# dcdr_3_0.net
KiCad netlist of a schematic drawn in EAGLE
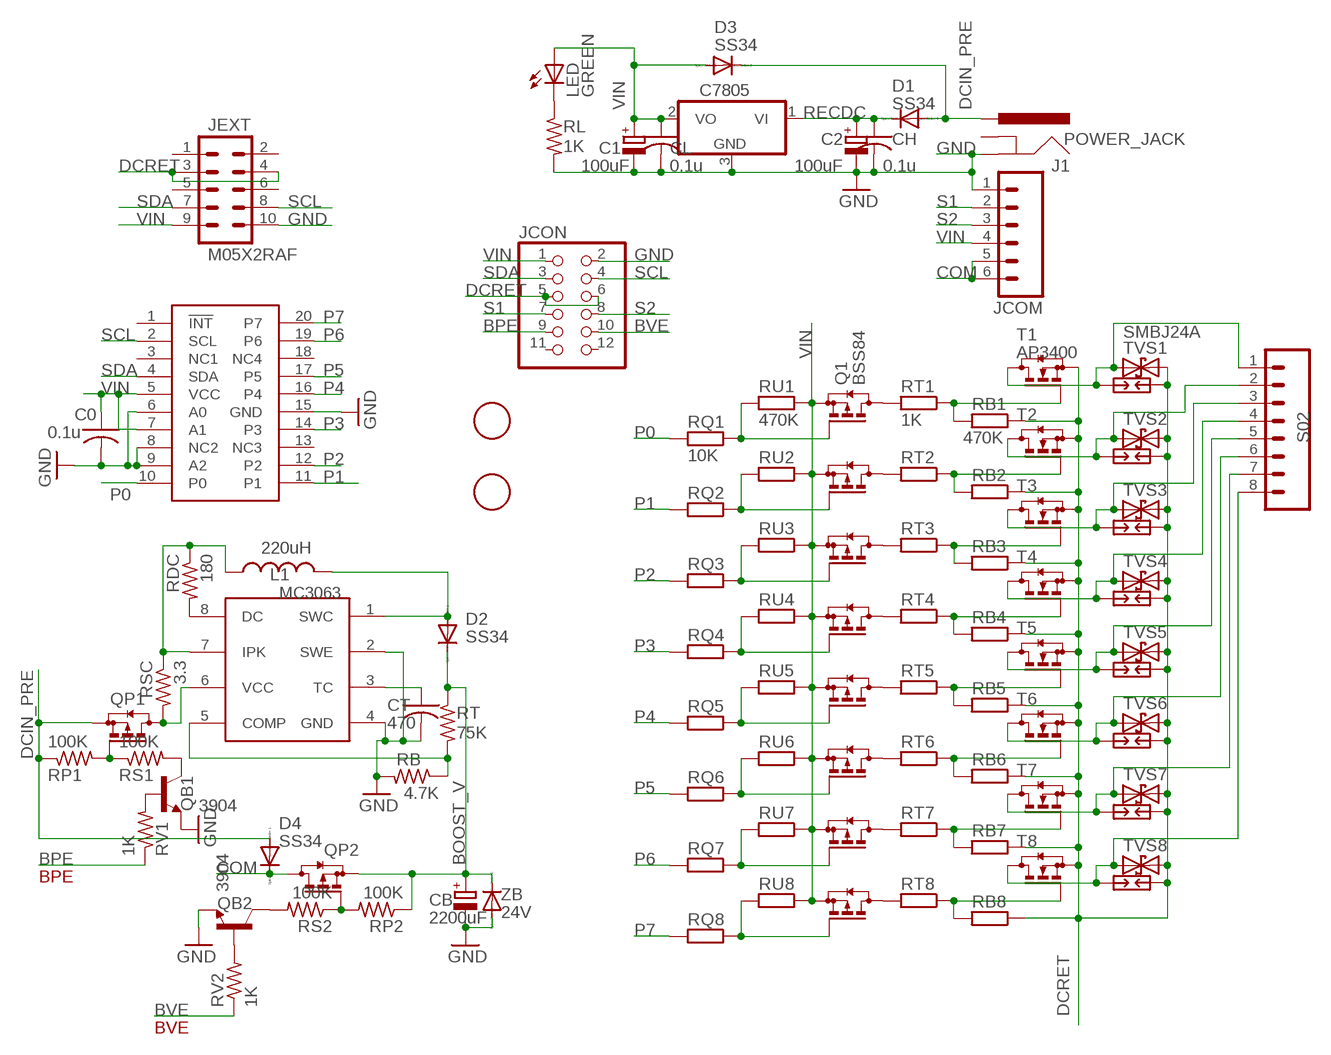
[diagram p0: schematic, sheet 1]

(export (version "E")
  (design (tool "Eeschema 10.0.6"))
  (components
    (comp (ref "C0")
      (value "0.1u")
      (footprint "eagle-import:C0603")
      (libsource (lib "eagle-import") (part "C-USC0603"))
    )
    (comp (ref "C1")
      (value "100uF")
      (footprint "eagle-import:PANASONIC_D")
      (libsource (lib "eagle-import") (part "resistor_CPOL-EUD"))
    )
    (comp (ref "C2")
      (value "100uF")
      (footprint "eagle-import:PANASONIC_D")
      (libsource (lib "eagle-import") (part "resistor_CPOL-EUD"))
    )
    (comp (ref "C7805")
      (value "7805DT")
      (footprint "eagle-import:TO252")
      (libsource (lib "eagle-import") (part "78DT05"))
    )
    (comp (ref "CB")
      (value "2200uF")
      (footprint "eagle-import:E7,5-16")
      (libsource (lib "eagle-import") (part "CPOL-EUE7.5-16"))
    )
    (comp (ref "CH")
      (value "0.1u")
      (footprint "eagle-import:C0603")
      (libsource (lib "eagle-import") (part "C-USC0603"))
    )
    (comp (ref "CL")
      (value "0.1u")
      (footprint "eagle-import:C0603")
      (libsource (lib "eagle-import") (part "C-USC0603"))
    )
    (comp (ref "CT")
      (value "470")
      (footprint "eagle-import:C0603K")
      (libsource (lib "eagle-import") (part "C-USC0603K"))
    )
    (comp (ref "D1")
      (value "SS34")
      (footprint "eagle-import:SMB")
      (libsource (lib "eagle-import") (part "DIODE-SMB"))
    )
    (comp (ref "D2")
      (value "SS34")
      (footprint "eagle-import:SMB")
      (libsource (lib "eagle-import") (part "DIODE-SMB"))
    )
    (comp (ref "D3")
      (value "SS34")
      (footprint "eagle-import:SMB")
      (libsource (lib "eagle-import") (part "DIODE-SMB"))
    )
    (comp (ref "D4")
      (value "SS34")
      (footprint "eagle-import:SMB")
      (libsource (lib "eagle-import") (part "DIODE-SMB"))
    )
    (comp (ref "J1")
      (value "POWER_JACK")
      (footprint "eagle-import:POWER_JACK_PTH_LOCK")
      (libsource (lib "eagle-import") (part "POWER_JACKPTH_LOCK"))
    )
    (comp (ref "JCOM")
      (value "M065MM")
      (footprint "eagle-import:SCREWTERMINAL-5MM-6")
      (libsource (lib "eagle-import") (part "M065MM"))
    )
    (comp (ref "JCON")
      (value "PINHD-2X6")
      (footprint "eagle-import:2X06")
      (libsource (lib "eagle-import") (part "PINHD-2X6"))
    )
    (comp (ref "JEXT")
      (value "M05X2RAF")
      (footprint "eagle-import:2X5-RAF")
      (libsource (lib "eagle-import") (part "M05X2RAF"))
    )
    (comp (ref "L1")
      (value "220uH")
      (footprint "eagle-import:CR54")
      (libsource (lib "eagle-import") (part "INDUCTORCR54"))
    )
    (comp (ref "LED")
      (value "GREEN")
      (footprint "eagle-import:CHIPLED_0805")
      (libsource (lib "eagle-import") (part "LEDCHIPLED_0805"))
    )
    (comp (ref "MC3063")
      (value "MC33063/MC34063D")
      (footprint "eagle-import:SO08")
      (libsource (lib "eagle-import") (part "MC33063/MC34063D"))
    )
    (comp (ref "PCF8574")
      (value "PCF8574")
      (footprint "eagle-import:SSOP20")
      (libsource (lib "eagle-import") (part "PCF8574"))
    )
    (comp (ref "Q1")
      (value "BSS84")
      (footprint "eagle-import:SOT23")
      (libsource (lib "eagle-import") (part "BSS84"))
    )
    (comp (ref "Q2")
      (value "BSS84")
      (footprint "eagle-import:SOT23")
      (libsource (lib "eagle-import") (part "BSS84"))
    )
    (comp (ref "Q3")
      (value "BSS84")
      (footprint "eagle-import:SOT23")
      (libsource (lib "eagle-import") (part "BSS84"))
    )
    (comp (ref "Q4")
      (value "BSS84")
      (footprint "eagle-import:SOT23")
      (libsource (lib "eagle-import") (part "BSS84"))
    )
    (comp (ref "Q5")
      (value "BSS84")
      (footprint "eagle-import:SOT23")
      (libsource (lib "eagle-import") (part "BSS84"))
    )
    (comp (ref "Q6")
      (value "BSS84")
      (footprint "eagle-import:SOT23")
      (libsource (lib "eagle-import") (part "BSS84"))
    )
    (comp (ref "Q7")
      (value "BSS84")
      (footprint "eagle-import:SOT23")
      (libsource (lib "eagle-import") (part "BSS84"))
    )
    (comp (ref "Q8")
      (value "BSS84")
      (footprint "eagle-import:SOT23")
      (libsource (lib "eagle-import") (part "BSS84"))
    )
    (comp (ref "QB1")
      (value "3904")
      (footprint "eagle-import:SOT23-3")
      (libsource (lib "eagle-import") (part "TRANSISTOR_NPNSOT23-3"))
    )
    (comp (ref "QB2")
      (value "3904")
      (footprint "eagle-import:SOT23-3")
      (libsource (lib "eagle-import") (part "TRANSISTOR_NPNSOT23-3"))
    )
    (comp (ref "QP1")
      (value "BSS84")
      (footprint "eagle-import:SOT23")
      (libsource (lib "eagle-import") (part "BSS84"))
    )
    (comp (ref "QP2")
      (value "BSS84")
      (footprint "eagle-import:SOT23")
      (libsource (lib "eagle-import") (part "BSS84"))
    )
    (comp (ref "RB")
      (value "4.7K")
      (footprint "eagle-import:R0603")
      (libsource (lib "eagle-import") (part "adafruitGood_R-US_R0603"))
    )
    (comp (ref "RB1")
      (value "470K")
      (footprint "eagle-import:R0603")
      (libsource (lib "eagle-import") (part "R-EU_R0603"))
    )
    (comp (ref "RB2")
      (value "470K")
      (footprint "eagle-import:R0603")
      (libsource (lib "eagle-import") (part "R-EU_R0603"))
    )
    (comp (ref "RB3")
      (value "470K")
      (footprint "eagle-import:R0603")
      (libsource (lib "eagle-import") (part "R-EU_R0603"))
    )
    (comp (ref "RB4")
      (value "470K")
      (footprint "eagle-import:R0603")
      (libsource (lib "eagle-import") (part "R-EU_R0603"))
    )
    (comp (ref "RB5")
      (value "470K")
      (footprint "eagle-import:R0603")
      (libsource (lib "eagle-import") (part "R-EU_R0603"))
    )
    (comp (ref "RB6")
      (value "470K")
      (footprint "eagle-import:R0603")
      (libsource (lib "eagle-import") (part "R-EU_R0603"))
    )
    (comp (ref "RB7")
      (value "470K")
      (footprint "eagle-import:R0603")
      (libsource (lib "eagle-import") (part "R-EU_R0603"))
    )
    (comp (ref "RB8")
      (value "470K")
      (footprint "eagle-import:R0603")
      (libsource (lib "eagle-import") (part "R-EU_R0603"))
    )
    (comp (ref "RDC")
      (value "180")
      (footprint "eagle-import:R0603")
      (libsource (lib "eagle-import") (part "adafruitGood_R-US_R0603"))
    )
    (comp (ref "RL")
      (value "1K")
      (footprint "eagle-import:R0603")
      (libsource (lib "eagle-import") (part "R-US_R0603"))
    )
    (comp (ref "RP1")
      (value "100K")
      (footprint "eagle-import:R0603")
      (libsource (lib "eagle-import") (part "adafruitGood_R-US_R0603"))
    )
    (comp (ref "RP2")
      (value "100K")
      (footprint "eagle-import:R0603")
      (libsource (lib "eagle-import") (part "adafruitGood_R-US_R0603"))
    )
    (comp (ref "RQ1")
      (value "10K")
      (footprint "eagle-import:R0603")
      (libsource (lib "eagle-import") (part "R-EU_R0603"))
    )
    (comp (ref "RQ2")
      (value "10K")
      (footprint "eagle-import:R0603")
      (libsource (lib "eagle-import") (part "R-EU_R0603"))
    )
    (comp (ref "RQ3")
      (value "10K")
      (footprint "eagle-import:R0603")
      (libsource (lib "eagle-import") (part "R-EU_R0603"))
    )
    (comp (ref "RQ4")
      (value "10K")
      (footprint "eagle-import:R0603")
      (libsource (lib "eagle-import") (part "R-EU_R0603"))
    )
    (comp (ref "RQ5")
      (value "10K")
      (footprint "eagle-import:R0603")
      (libsource (lib "eagle-import") (part "R-EU_R0603"))
    )
    (comp (ref "RQ6")
      (value "10K")
      (footprint "eagle-import:R0603")
      (libsource (lib "eagle-import") (part "R-EU_R0603"))
    )
    (comp (ref "RQ7")
      (value "10K")
      (footprint "eagle-import:R0603")
      (libsource (lib "eagle-import") (part "R-EU_R0603"))
    )
    (comp (ref "RQ8")
      (value "10K")
      (footprint "eagle-import:R0603")
      (libsource (lib "eagle-import") (part "R-EU_R0603"))
    )
    (comp (ref "RS1")
      (value "100K")
      (footprint "eagle-import:R0603")
      (libsource (lib "eagle-import") (part "adafruitGood_R-US_R0603"))
    )
    (comp (ref "RS2")
      (value "100K")
      (footprint "eagle-import:R0603")
      (libsource (lib "eagle-import") (part "adafruitGood_R-US_R0603"))
    )
    (comp (ref "RSC")
      (value "3.3")
      (footprint "eagle-import:R0603")
      (libsource (lib "eagle-import") (part "adafruitGood_R-US_R0603"))
    )
    (comp (ref "RT")
      (value "75K")
      (footprint "eagle-import:R0603")
      (libsource (lib "eagle-import") (part "adafruitGood_R-US_R0603"))
    )
    (comp (ref "RT1")
      (value "1K")
      (footprint "eagle-import:R0603")
      (libsource (lib "eagle-import") (part "R-EU_R0603"))
    )
    (comp (ref "RT2")
      (value "1K")
      (footprint "eagle-import:R0603")
      (libsource (lib "eagle-import") (part "R-EU_R0603"))
    )
    (comp (ref "RT3")
      (value "1K")
      (footprint "eagle-import:R0603")
      (libsource (lib "eagle-import") (part "R-EU_R0603"))
    )
    (comp (ref "RT4")
      (value "1K")
      (footprint "eagle-import:R0603")
      (libsource (lib "eagle-import") (part "R-EU_R0603"))
    )
    (comp (ref "RT5")
      (value "1K")
      (footprint "eagle-import:R0603")
      (libsource (lib "eagle-import") (part "R-EU_R0603"))
    )
    (comp (ref "RT6")
      (value "1K")
      (footprint "eagle-import:R0603")
      (libsource (lib "eagle-import") (part "R-EU_R0603"))
    )
    (comp (ref "RT7")
      (value "1K")
      (footprint "eagle-import:R0603")
      (libsource (lib "eagle-import") (part "R-EU_R0603"))
    )
    (comp (ref "RT8")
      (value "1K")
      (footprint "eagle-import:R0603")
      (libsource (lib "eagle-import") (part "R-EU_R0603"))
    )
    (comp (ref "RU1")
      (value "470K")
      (footprint "eagle-import:R0603")
      (libsource (lib "eagle-import") (part "R-EU_R0603"))
    )
    (comp (ref "RU2")
      (value "470K")
      (footprint "eagle-import:R0603")
      (libsource (lib "eagle-import") (part "R-EU_R0603"))
    )
    (comp (ref "RU3")
      (value "470K")
      (footprint "eagle-import:R0603")
      (libsource (lib "eagle-import") (part "R-EU_R0603"))
    )
    (comp (ref "RU4")
      (value "470K")
      (footprint "eagle-import:R0603")
      (libsource (lib "eagle-import") (part "R-EU_R0603"))
    )
    (comp (ref "RU5")
      (value "470K")
      (footprint "eagle-import:R0603")
      (libsource (lib "eagle-import") (part "R-EU_R0603"))
    )
    (comp (ref "RU6")
      (value "470K")
      (footprint "eagle-import:R0603")
      (libsource (lib "eagle-import") (part "R-EU_R0603"))
    )
    (comp (ref "RU7")
      (value "470K")
      (footprint "eagle-import:R0603")
      (libsource (lib "eagle-import") (part "R-EU_R0603"))
    )
    (comp (ref "RU8")
      (value "470K")
      (footprint "eagle-import:R0603")
      (libsource (lib "eagle-import") (part "R-EU_R0603"))
    )
    (comp (ref "RV1")
      (value "1K")
      (footprint "eagle-import:R0603")
      (libsource (lib "eagle-import") (part "adafruitGood_R-US_R0603"))
    )
    (comp (ref "RV2")
      (value "1K")
      (footprint "eagle-import:R0603")
      (libsource (lib "eagle-import") (part "adafruitGood_R-US_R0603"))
    )
    (comp (ref "S02")
      (value "M085MM-8")
      (footprint "eagle-import:SCREWTERMINAL-5MM-8")
      (libsource (lib "eagle-import") (part "M085MM-8"))
    )
    (comp (ref "SP1")
      (value "PCB-SGAP")
      (footprint "eagle-import:PCB-SGAP")
      (libsource (lib "eagle-import") (part "PCB-SGAP"))
    )
    (comp (ref "SP2")
      (value "PCB-SGAP")
      (footprint "eagle-import:PCB-SGAP")
      (libsource (lib "eagle-import") (part "PCB-SGAP"))
    )
    (comp (ref "SP3")
      (value "PCB-SGAP")
      (footprint "eagle-import:PCB-SGAP")
      (libsource (lib "eagle-import") (part "PCB-SGAP"))
    )
    (comp (ref "SP4")
      (value "PCB-SGAP")
      (footprint "eagle-import:PCB-SGAP")
      (libsource (lib "eagle-import") (part "PCB-SGAP"))
    )
    (comp (ref "SP5")
      (value "PCB-SGAP")
      (footprint "eagle-import:PCB-SGAP")
      (libsource (lib "eagle-import") (part "PCB-SGAP"))
    )
    (comp (ref "SP6")
      (value "PCB-SGAP")
      (footprint "eagle-import:PCB-SGAP")
      (libsource (lib "eagle-import") (part "PCB-SGAP"))
    )
    (comp (ref "SP7")
      (value "PCB-SGAP")
      (footprint "eagle-import:PCB-SGAP")
      (libsource (lib "eagle-import") (part "PCB-SGAP"))
    )
    (comp (ref "SP8")
      (value "PCB-SGAP")
      (footprint "eagle-import:PCB-SGAP")
      (libsource (lib "eagle-import") (part "PCB-SGAP"))
    )
    (comp (ref "T1")
      (value "AP3400")
      (footprint "eagle-import:SOT23")
      (libsource (lib "eagle-import") (part "BSS123"))
    )
    (comp (ref "T2")
      (value "BSS123")
      (footprint "eagle-import:SOT23")
      (libsource (lib "eagle-import") (part "BSS123"))
    )
    (comp (ref "T3")
      (value "BSS123")
      (footprint "eagle-import:SOT23")
      (libsource (lib "eagle-import") (part "BSS123"))
    )
    (comp (ref "T4")
      (value "BSS123")
      (footprint "eagle-import:SOT23")
      (libsource (lib "eagle-import") (part "BSS123"))
    )
    (comp (ref "T5")
      (value "BSS123")
      (footprint "eagle-import:SOT23")
      (libsource (lib "eagle-import") (part "BSS123"))
    )
    (comp (ref "T6")
      (value "BSS123")
      (footprint "eagle-import:SOT23")
      (libsource (lib "eagle-import") (part "BSS123"))
    )
    (comp (ref "T7")
      (value "BSS123")
      (footprint "eagle-import:SOT23")
      (libsource (lib "eagle-import") (part "BSS123"))
    )
    (comp (ref "T8")
      (value "BSS123")
      (footprint "eagle-import:SOT23")
      (libsource (lib "eagle-import") (part "BSS123"))
    )
    (comp (ref "TVS1")
      (value "SMBJ24A")
      (footprint "eagle-import:SMB")
      (libsource (lib "eagle-import") (part "TVSSMB"))
    )
    (comp (ref "TVS2")
      (value "TVSSMB")
      (footprint "eagle-import:SMB")
      (libsource (lib "eagle-import") (part "TVSSMB"))
    )
    (comp (ref "TVS3")
      (value "TVSSMB")
      (footprint "eagle-import:SMB")
      (libsource (lib "eagle-import") (part "TVSSMB"))
    )
    (comp (ref "TVS4")
      (value "TVSSMB")
      (footprint "eagle-import:SMB")
      (libsource (lib "eagle-import") (part "TVSSMB"))
    )
    (comp (ref "TVS5")
      (value "TVSSMB")
      (footprint "eagle-import:SMB")
      (libsource (lib "eagle-import") (part "TVSSMB"))
    )
    (comp (ref "TVS6")
      (value "TVSSMB")
      (footprint "eagle-import:SMB")
      (libsource (lib "eagle-import") (part "TVSSMB"))
    )
    (comp (ref "TVS7")
      (value "TVSSMB")
      (footprint "eagle-import:SMB")
      (libsource (lib "eagle-import") (part "TVSSMB"))
    )
    (comp (ref "TVS8")
      (value "TVSSMB")
      (footprint "eagle-import:SMB")
      (libsource (lib "eagle-import") (part "TVSSMB"))
    )
    (comp (ref "U$1")
      (value "FIDUCIAL")
      (footprint "eagle-import:FIDUCIAL_1MM")
      (libsource (lib "eagle-import") (part "FIDUCIAL"))
    )
    (comp (ref "U$2")
      (value "FIDUCIAL")
      (footprint "eagle-import:FIDUCIAL_1MM")
      (libsource (lib "eagle-import") (part "FIDUCIAL"))
    )
    (comp (ref "ZB")
      (value "24V")
      (footprint "eagle-import:MINIMELF")
      (libsource (lib "eagle-import") (part "DIODE-MINIMELF"))
    )
  )
  (nets
    (net (code "1") (name "/BOOST_V") (class "Default")
      (node (ref "CB") (pin "+") (pinfunction "+_+") (pintype "passive"))
      (node (ref "D2") (pin "C") (pinfunction "C_C") (pintype "passive"))
      (node (ref "QP2") (pin "2") (pinfunction "S_2") (pintype "passive"))
      (node (ref "RP2") (pin "1") (pinfunction "1_1") (pintype "passive"))
      (node (ref "RT") (pin "1") (pinfunction "1_1") (pintype "passive"))
      (node (ref "ZB") (pin "C") (pinfunction "C_C") (pintype "passive"))
    )
    (net (code "2") (name "/BPE") (class "Default")
      (node (ref "JCON") (pin "9") (pinfunction "9_9") (pintype "passive"))
      (node (ref "RV1") (pin "1") (pinfunction "1_1") (pintype "passive"))
    )
    (net (code "3") (name "/BVE") (class "Default")
      (node (ref "JCON") (pin "10") (pinfunction "10_10") (pintype "passive"))
      (node (ref "RV2") (pin "1") (pinfunction "1_1") (pintype "passive"))
    )
    (net (code "4") (name "/COM") (class "Default")
      (node (ref "D4") (pin "C") (pinfunction "C_C") (pintype "passive"))
      (node (ref "JCOM") (pin "5") (pinfunction "5_5") (pintype "passive"))
      (node (ref "JCOM") (pin "6") (pinfunction "6_6") (pintype "passive"))
      (node (ref "QP2") (pin "3") (pinfunction "D_3") (pintype "passive"))
    )
    (net (code "5") (name "/DCIN_PRE") (class "Default")
      (node (ref "D1") (pin "A") (pinfunction "A_A") (pintype "passive"))
      (node (ref "D3") (pin "C") (pinfunction "C_C") (pintype "passive"))
      (node (ref "D4") (pin "A") (pinfunction "A_A") (pintype "passive"))
      (node (ref "J1") (pin "PWR") (pinfunction "PWR_PWR") (pintype "bidirectional"))
      (node (ref "QP1") (pin "2") (pinfunction "S_2") (pintype "passive"))
      (node (ref "RP1") (pin "1") (pinfunction "1_1") (pintype "passive"))
    )
    (net (code "6") (name "/DCRET") (class "Default")
      (node (ref "JCON") (pin "5") (pinfunction "5_5") (pintype "passive"))
      (node (ref "JCON") (pin "6") (pinfunction "6_6") (pintype "passive"))
      (node (ref "JEXT") (pin "3") (pinfunction "3_3") (pintype "passive"))
      (node (ref "JEXT") (pin "4") (pinfunction "4_4") (pintype "passive"))
      (node (ref "RB1") (pin "1") (pinfunction "1_1") (pintype "passive"))
      (node (ref "RB2") (pin "1") (pinfunction "1_1") (pintype "passive"))
      (node (ref "RB3") (pin "1") (pinfunction "1_1") (pintype "passive"))
      (node (ref "RB4") (pin "1") (pinfunction "1_1") (pintype "passive"))
      (node (ref "RB5") (pin "1") (pinfunction "1_1") (pintype "passive"))
      (node (ref "RB6") (pin "1") (pinfunction "1_1") (pintype "passive"))
      (node (ref "RB7") (pin "1") (pinfunction "1_1") (pintype "passive"))
      (node (ref "RB8") (pin "1") (pinfunction "1_1") (pintype "passive"))
      (node (ref "SP1") (pin "1") (pinfunction "1_1") (pintype "passive"))
      (node (ref "SP2") (pin "1") (pinfunction "1_1") (pintype "passive"))
      (node (ref "SP3") (pin "1") (pinfunction "1_1") (pintype "passive"))
      (node (ref "SP4") (pin "1") (pinfunction "1_1") (pintype "passive"))
      (node (ref "SP5") (pin "1") (pinfunction "1_1") (pintype "passive"))
      (node (ref "SP6") (pin "1") (pinfunction "1_1") (pintype "passive"))
      (node (ref "SP7") (pin "1") (pinfunction "1_1") (pintype "passive"))
      (node (ref "SP8") (pin "1") (pinfunction "1_1") (pintype "passive"))
      (node (ref "T1") (pin "2") (pinfunction "S_2") (pintype "passive"))
      (node (ref "T2") (pin "2") (pinfunction "S_2") (pintype "passive"))
      (node (ref "T3") (pin "2") (pinfunction "S_2") (pintype "passive"))
      (node (ref "T4") (pin "2") (pinfunction "S_2") (pintype "passive"))
      (node (ref "T5") (pin "2") (pinfunction "S_2") (pintype "passive"))
      (node (ref "T6") (pin "2") (pinfunction "S_2") (pintype "passive"))
      (node (ref "T7") (pin "2") (pinfunction "S_2") (pintype "passive"))
      (node (ref "T8") (pin "2") (pinfunction "S_2") (pintype "passive"))
      (node (ref "TVS1") (pin "C") (pinfunction "C_C") (pintype "passive"))
      (node (ref "TVS2") (pin "C") (pinfunction "C_C") (pintype "passive"))
      (node (ref "TVS3") (pin "C") (pinfunction "C_C") (pintype "passive"))
      (node (ref "TVS4") (pin "C") (pinfunction "C_C") (pintype "passive"))
      (node (ref "TVS5") (pin "C") (pinfunction "C_C") (pintype "passive"))
      (node (ref "TVS6") (pin "C") (pinfunction "C_C") (pintype "passive"))
      (node (ref "TVS7") (pin "C") (pinfunction "C_C") (pintype "passive"))
      (node (ref "TVS8") (pin "C") (pinfunction "C_C") (pintype "passive"))
    )
    (net (code "7") (name "/P0") (class "Default")
      (node (ref "PCF8574") (pin "10") (pinfunction "P0_10") (pintype "bidirectional"))
      (node (ref "RQ1") (pin "2") (pinfunction "2_2") (pintype "passive"))
    )
    (net (code "8") (name "/P1") (class "Default")
      (node (ref "PCF8574") (pin "11") (pinfunction "P1_11") (pintype "bidirectional"))
      (node (ref "RQ2") (pin "2") (pinfunction "2_2") (pintype "passive"))
    )
    (net (code "9") (name "/P2") (class "Default")
      (node (ref "PCF8574") (pin "12") (pinfunction "P2_12") (pintype "bidirectional"))
      (node (ref "RQ3") (pin "2") (pinfunction "2_2") (pintype "passive"))
    )
    (net (code "10") (name "/P3") (class "Default")
      (node (ref "PCF8574") (pin "14") (pinfunction "P3_14") (pintype "bidirectional"))
      (node (ref "RQ4") (pin "2") (pinfunction "2_2") (pintype "passive"))
    )
    (net (code "11") (name "/P4") (class "Default")
      (node (ref "PCF8574") (pin "16") (pinfunction "P4_16") (pintype "bidirectional"))
      (node (ref "RQ5") (pin "2") (pinfunction "2_2") (pintype "passive"))
    )
    (net (code "12") (name "/P5") (class "Default")
      (node (ref "PCF8574") (pin "17") (pinfunction "P5_17") (pintype "bidirectional"))
      (node (ref "RQ6") (pin "2") (pinfunction "2_2") (pintype "passive"))
    )
    (net (code "13") (name "/P6") (class "Default")
      (node (ref "PCF8574") (pin "19") (pinfunction "P6_19") (pintype "bidirectional"))
      (node (ref "RQ7") (pin "2") (pinfunction "2_2") (pintype "passive"))
    )
    (net (code "14") (name "/P7") (class "Default")
      (node (ref "PCF8574") (pin "20") (pinfunction "P7_20") (pintype "bidirectional"))
      (node (ref "RQ8") (pin "2") (pinfunction "2_2") (pintype "passive"))
    )
    (net (code "15") (name "/RECDC") (class "Default")
      (node (ref "C2") (pin "+") (pinfunction "+_+") (pintype "passive"))
      (node (ref "C7805") (pin "1") (pinfunction "VI_1") (pintype "input"))
      (node (ref "CH") (pin "1") (pinfunction "1_1") (pintype "passive"))
      (node (ref "D1") (pin "C") (pinfunction "C_C") (pintype "passive"))
    )
    (net (code "16") (name "/S1") (class "Default")
      (node (ref "JCOM") (pin "2") (pinfunction "2_2") (pintype "passive"))
      (node (ref "JCON") (pin "7") (pinfunction "7_7") (pintype "passive"))
    )
    (net (code "17") (name "/S2") (class "Default")
      (node (ref "JCOM") (pin "3") (pinfunction "3_3") (pintype "passive"))
      (node (ref "JCON") (pin "8") (pinfunction "8_8") (pintype "passive"))
    )
    (net (code "18") (name "/SCL") (class "Default")
      (node (ref "JCON") (pin "4") (pinfunction "4_4") (pintype "passive"))
      (node (ref "JEXT") (pin "8") (pinfunction "8_8") (pintype "passive"))
      (node (ref "PCF8574") (pin "2") (pinfunction "SCL_2") (pintype "bidirectional"))
    )
    (net (code "19") (name "/SDA") (class "Default")
      (node (ref "JCON") (pin "3") (pinfunction "3_3") (pintype "passive"))
      (node (ref "JEXT") (pin "7") (pinfunction "7_7") (pintype "passive"))
      (node (ref "PCF8574") (pin "4") (pinfunction "SDA_4") (pintype "bidirectional"))
    )
    (net (code "20") (name "/VIN") (class "Default")
      (node (ref "C0") (pin "1") (pinfunction "1_1") (pintype "passive"))
      (node (ref "C1") (pin "+") (pinfunction "+_+") (pintype "passive"))
      (node (ref "C7805") (pin "2") (pinfunction "VO_2") (pintype "passive"))
      (node (ref "CL") (pin "1") (pinfunction "1_1") (pintype "passive"))
      (node (ref "D3") (pin "A") (pinfunction "A_A") (pintype "passive"))
      (node (ref "JCOM") (pin "4") (pinfunction "4_4") (pintype "passive"))
      (node (ref "JCON") (pin "1") (pinfunction "1_1") (pintype "passive"))
      (node (ref "JEXT") (pin "9") (pinfunction "9_9") (pintype "passive"))
      (node (ref "LED") (pin "A") (pinfunction "A_A") (pintype "passive"))
      (node (ref "PCF8574") (pin "5") (pinfunction "VCC_5") (pintype "power_in"))
      (node (ref "PCF8574") (pin "7") (pinfunction "A1_7") (pintype "bidirectional"))
      (node (ref "Q1") (pin "2") (pinfunction "S_2") (pintype "passive"))
      (node (ref "Q2") (pin "2") (pinfunction "S_2") (pintype "passive"))
      (node (ref "Q3") (pin "2") (pinfunction "S_2") (pintype "passive"))
      (node (ref "Q4") (pin "2") (pinfunction "S_2") (pintype "passive"))
      (node (ref "Q5") (pin "2") (pinfunction "S_2") (pintype "passive"))
      (node (ref "Q6") (pin "2") (pinfunction "S_2") (pintype "passive"))
      (node (ref "Q7") (pin "2") (pinfunction "S_2") (pintype "passive"))
      (node (ref "Q8") (pin "2") (pinfunction "S_2") (pintype "passive"))
      (node (ref "RU1") (pin "1") (pinfunction "1_1") (pintype "passive"))
      (node (ref "RU2") (pin "1") (pinfunction "1_1") (pintype "passive"))
      (node (ref "RU3") (pin "1") (pinfunction "1_1") (pintype "passive"))
      (node (ref "RU4") (pin "1") (pinfunction "1_1") (pintype "passive"))
      (node (ref "RU5") (pin "1") (pinfunction "1_1") (pintype "passive"))
      (node (ref "RU6") (pin "1") (pinfunction "1_1") (pintype "passive"))
      (node (ref "RU7") (pin "1") (pinfunction "1_1") (pintype "passive"))
      (node (ref "RU8") (pin "1") (pinfunction "1_1") (pintype "passive"))
    )
    (net (code "21") (name "GND") (class "Default")
      (node (ref "C0") (pin "2") (pinfunction "2_2") (pintype "passive"))
      (node (ref "C1") (pin "-") (pinfunction "-_-") (pintype "passive"))
      (node (ref "C2") (pin "-") (pinfunction "-_-") (pintype "passive"))
      (node (ref "C7805") (pin "3") (pinfunction "GND_3") (pintype "passive"))
      (node (ref "CB") (pin "-") (pinfunction "-_-") (pintype "passive"))
      (node (ref "CH") (pin "2") (pinfunction "2_2") (pintype "passive"))
      (node (ref "CL") (pin "2") (pinfunction "2_2") (pintype "passive"))
      (node (ref "CT") (pin "2") (pinfunction "2_2") (pintype "passive"))
      (node (ref "J1") (pin "GND") (pinfunction "GND_GND") (pintype "bidirectional"))
      (node (ref "JCOM") (pin "1") (pinfunction "1_1") (pintype "passive"))
      (node (ref "JCON") (pin "2") (pinfunction "2_2") (pintype "passive"))
      (node (ref "JEXT") (pin "10") (pinfunction "10_10") (pintype "passive"))
      (node (ref "MC3063") (pin "2") (pinfunction "SWE_2") (pintype "input"))
      (node (ref "MC3063") (pin "4") (pinfunction "GND_4") (pintype "power_in"))
      (node (ref "PCF8574") (pin "15") (pinfunction "GND_15") (pintype "power_in"))
      (node (ref "PCF8574") (pin "6") (pinfunction "A0_6") (pintype "bidirectional"))
      (node (ref "PCF8574") (pin "8") (pinfunction "NC2_8") (pintype "bidirectional"))
      (node (ref "PCF8574") (pin "9") (pinfunction "A2_9") (pintype "bidirectional"))
      (node (ref "QB1") (pin "2") (pinfunction "E_2") (pintype "passive"))
      (node (ref "QB2") (pin "2") (pinfunction "E_2") (pintype "passive"))
      (node (ref "RB") (pin "2") (pinfunction "2_2") (pintype "passive"))
      (node (ref "RL") (pin "2") (pinfunction "2_2") (pintype "passive"))
      (node (ref "ZB") (pin "A") (pinfunction "A_A") (pintype "passive"))
    )
    (net (code "22") (name "Net-(L1-1)") (class "Default")
      (node (ref "L1") (pin "P$1") (pinfunction "1_P$1") (pintype "passive"))
      (node (ref "MC3063") (pin "7") (pinfunction "IPK_7") (pintype "bidirectional"))
      (node (ref "RDC") (pin "1") (pinfunction "1_1") (pintype "passive"))
      (node (ref "RSC") (pin "1") (pinfunction "1_1") (pintype "passive"))
    )
    (net (code "23") (name "Net-(L1-2)") (class "Default")
      (node (ref "D2") (pin "A") (pinfunction "A_A") (pintype "passive"))
      (node (ref "L1") (pin "P$2") (pinfunction "2_P$2") (pintype "passive"))
      (node (ref "MC3063") (pin "1") (pinfunction "SWC_1") (pintype "input"))
    )
    (net (code "24") (name "Net-(LED-PadC)") (class "Default")
      (node (ref "LED") (pin "C") (pinfunction "C_C") (pintype "passive"))
      (node (ref "RL") (pin "1") (pinfunction "1_1") (pintype "passive"))
    )
    (net (code "25") (name "Net-(MC3063-COMP)") (class "Default")
      (node (ref "MC3063") (pin "5") (pinfunction "COMP_5") (pintype "input"))
      (node (ref "RB") (pin "1") (pinfunction "1_1") (pintype "passive"))
      (node (ref "RT") (pin "2") (pinfunction "2_2") (pintype "passive"))
    )
    (net (code "26") (name "Net-(MC3063-DC)") (class "Default")
      (node (ref "MC3063") (pin "8") (pinfunction "DC_8") (pintype "input"))
      (node (ref "RDC") (pin "2") (pinfunction "2_2") (pintype "passive"))
    )
    (net (code "27") (name "Net-(MC3063-TC)") (class "Default")
      (node (ref "CT") (pin "1") (pinfunction "1_1") (pintype "passive"))
      (node (ref "MC3063") (pin "3") (pinfunction "TC_3") (pintype "input"))
    )
    (net (code "28") (name "Net-(MC3063-VCC)") (class "Default")
      (node (ref "MC3063") (pin "6") (pinfunction "VCC_6") (pintype "power_in"))
      (node (ref "QP1") (pin "3") (pinfunction "D_3") (pintype "passive"))
      (node (ref "RSC") (pin "2") (pinfunction "2_2") (pintype "passive"))
    )
    (net (code "29") (name "Net-(Q1-D)") (class "Default")
      (node (ref "Q1") (pin "3") (pinfunction "D_3") (pintype "passive"))
      (node (ref "RT1") (pin "2") (pinfunction "2_2") (pintype "passive"))
    )
    (net (code "30") (name "Net-(Q1-G)") (class "Default")
      (node (ref "Q1") (pin "1") (pinfunction "G_1") (pintype "passive"))
      (node (ref "RQ1") (pin "1") (pinfunction "1_1") (pintype "passive"))
      (node (ref "RU1") (pin "2") (pinfunction "2_2") (pintype "passive"))
    )
    (net (code "31") (name "Net-(Q2-D)") (class "Default")
      (node (ref "Q2") (pin "3") (pinfunction "D_3") (pintype "passive"))
      (node (ref "RT2") (pin "2") (pinfunction "2_2") (pintype "passive"))
    )
    (net (code "32") (name "Net-(Q2-G)") (class "Default")
      (node (ref "Q2") (pin "1") (pinfunction "G_1") (pintype "passive"))
      (node (ref "RQ2") (pin "1") (pinfunction "1_1") (pintype "passive"))
      (node (ref "RU2") (pin "2") (pinfunction "2_2") (pintype "passive"))
    )
    (net (code "33") (name "Net-(Q3-D)") (class "Default")
      (node (ref "Q3") (pin "3") (pinfunction "D_3") (pintype "passive"))
      (node (ref "RT3") (pin "2") (pinfunction "2_2") (pintype "passive"))
    )
    (net (code "34") (name "Net-(Q3-G)") (class "Default")
      (node (ref "Q3") (pin "1") (pinfunction "G_1") (pintype "passive"))
      (node (ref "RQ3") (pin "1") (pinfunction "1_1") (pintype "passive"))
      (node (ref "RU3") (pin "2") (pinfunction "2_2") (pintype "passive"))
    )
    (net (code "35") (name "Net-(Q4-D)") (class "Default")
      (node (ref "Q4") (pin "3") (pinfunction "D_3") (pintype "passive"))
      (node (ref "RT4") (pin "2") (pinfunction "2_2") (pintype "passive"))
    )
    (net (code "36") (name "Net-(Q4-G)") (class "Default")
      (node (ref "Q4") (pin "1") (pinfunction "G_1") (pintype "passive"))
      (node (ref "RQ4") (pin "1") (pinfunction "1_1") (pintype "passive"))
      (node (ref "RU4") (pin "2") (pinfunction "2_2") (pintype "passive"))
    )
    (net (code "37") (name "Net-(Q5-D)") (class "Default")
      (node (ref "Q5") (pin "3") (pinfunction "D_3") (pintype "passive"))
      (node (ref "RT5") (pin "2") (pinfunction "2_2") (pintype "passive"))
    )
    (net (code "38") (name "Net-(Q5-G)") (class "Default")
      (node (ref "Q5") (pin "1") (pinfunction "G_1") (pintype "passive"))
      (node (ref "RQ5") (pin "1") (pinfunction "1_1") (pintype "passive"))
      (node (ref "RU5") (pin "2") (pinfunction "2_2") (pintype "passive"))
    )
    (net (code "39") (name "Net-(Q6-D)") (class "Default")
      (node (ref "Q6") (pin "3") (pinfunction "D_3") (pintype "passive"))
      (node (ref "RT6") (pin "2") (pinfunction "2_2") (pintype "passive"))
    )
    (net (code "40") (name "Net-(Q6-G)") (class "Default")
      (node (ref "Q6") (pin "1") (pinfunction "G_1") (pintype "passive"))
      (node (ref "RQ6") (pin "1") (pinfunction "1_1") (pintype "passive"))
      (node (ref "RU6") (pin "2") (pinfunction "2_2") (pintype "passive"))
    )
    (net (code "41") (name "Net-(Q7-D)") (class "Default")
      (node (ref "Q7") (pin "3") (pinfunction "D_3") (pintype "passive"))
      (node (ref "RT7") (pin "2") (pinfunction "2_2") (pintype "passive"))
    )
    (net (code "42") (name "Net-(Q7-G)") (class "Default")
      (node (ref "Q7") (pin "1") (pinfunction "G_1") (pintype "passive"))
      (node (ref "RQ7") (pin "1") (pinfunction "1_1") (pintype "passive"))
      (node (ref "RU7") (pin "2") (pinfunction "2_2") (pintype "passive"))
    )
    (net (code "43") (name "Net-(Q8-D)") (class "Default")
      (node (ref "Q8") (pin "3") (pinfunction "D_3") (pintype "passive"))
      (node (ref "RT8") (pin "2") (pinfunction "2_2") (pintype "passive"))
    )
    (net (code "44") (name "Net-(Q8-G)") (class "Default")
      (node (ref "Q8") (pin "1") (pinfunction "G_1") (pintype "passive"))
      (node (ref "RQ8") (pin "1") (pinfunction "1_1") (pintype "passive"))
      (node (ref "RU8") (pin "2") (pinfunction "2_2") (pintype "passive"))
    )
    (net (code "45") (name "Net-(QB1-B)") (class "Default")
      (node (ref "QB1") (pin "1") (pinfunction "B_1") (pintype "passive"))
      (node (ref "RV1") (pin "2") (pinfunction "2_2") (pintype "passive"))
    )
    (net (code "46") (name "Net-(QB1-C)") (class "Default")
      (node (ref "QB1") (pin "3") (pinfunction "C_3") (pintype "passive"))
      (node (ref "RS1") (pin "2") (pinfunction "2_2") (pintype "passive"))
    )
    (net (code "47") (name "Net-(QB2-B)") (class "Default")
      (node (ref "QB2") (pin "1") (pinfunction "B_1") (pintype "passive"))
      (node (ref "RV2") (pin "2") (pinfunction "2_2") (pintype "passive"))
    )
    (net (code "48") (name "Net-(QB2-C)") (class "Default")
      (node (ref "QB2") (pin "3") (pinfunction "C_3") (pintype "passive"))
      (node (ref "RS2") (pin "2") (pinfunction "2_2") (pintype "passive"))
    )
    (net (code "49") (name "Net-(QP1-G)") (class "Default")
      (node (ref "QP1") (pin "1") (pinfunction "G_1") (pintype "passive"))
      (node (ref "RP1") (pin "2") (pinfunction "2_2") (pintype "passive"))
      (node (ref "RS1") (pin "1") (pinfunction "1_1") (pintype "passive"))
    )
    (net (code "50") (name "Net-(QP2-G)") (class "Default")
      (node (ref "QP2") (pin "1") (pinfunction "G_1") (pintype "passive"))
      (node (ref "RP2") (pin "2") (pinfunction "2_2") (pintype "passive"))
      (node (ref "RS2") (pin "1") (pinfunction "1_1") (pintype "passive"))
    )
    (net (code "51") (name "Net-(T1-D)") (class "Default")
      (node (ref "S02") (pin "1") (pinfunction "1_1") (pintype "passive"))
      (node (ref "SP1") (pin "2") (pinfunction "2_2") (pintype "passive"))
      (node (ref "T1") (pin "3") (pinfunction "D_3") (pintype "passive"))
      (node (ref "TVS1") (pin "A") (pinfunction "A_A") (pintype "passive"))
    )
    (net (code "52") (name "Net-(T1-G)") (class "Default")
      (node (ref "RB1") (pin "2") (pinfunction "2_2") (pintype "passive"))
      (node (ref "RT1") (pin "1") (pinfunction "1_1") (pintype "passive"))
      (node (ref "T1") (pin "1") (pinfunction "G_1") (pintype "passive"))
    )
    (net (code "53") (name "Net-(T2-D)") (class "Default")
      (node (ref "S02") (pin "2") (pinfunction "2_2") (pintype "passive"))
      (node (ref "SP2") (pin "2") (pinfunction "2_2") (pintype "passive"))
      (node (ref "T2") (pin "3") (pinfunction "D_3") (pintype "passive"))
      (node (ref "TVS2") (pin "A") (pinfunction "A_A") (pintype "passive"))
    )
    (net (code "54") (name "Net-(T2-G)") (class "Default")
      (node (ref "RB2") (pin "2") (pinfunction "2_2") (pintype "passive"))
      (node (ref "RT2") (pin "1") (pinfunction "1_1") (pintype "passive"))
      (node (ref "T2") (pin "1") (pinfunction "G_1") (pintype "passive"))
    )
    (net (code "55") (name "Net-(T3-D)") (class "Default")
      (node (ref "S02") (pin "3") (pinfunction "3_3") (pintype "passive"))
      (node (ref "SP3") (pin "2") (pinfunction "2_2") (pintype "passive"))
      (node (ref "T3") (pin "3") (pinfunction "D_3") (pintype "passive"))
      (node (ref "TVS3") (pin "A") (pinfunction "A_A") (pintype "passive"))
    )
    (net (code "56") (name "Net-(T3-G)") (class "Default")
      (node (ref "RB3") (pin "2") (pinfunction "2_2") (pintype "passive"))
      (node (ref "RT3") (pin "1") (pinfunction "1_1") (pintype "passive"))
      (node (ref "T3") (pin "1") (pinfunction "G_1") (pintype "passive"))
    )
    (net (code "57") (name "Net-(T4-D)") (class "Default")
      (node (ref "S02") (pin "4") (pinfunction "4_4") (pintype "passive"))
      (node (ref "SP4") (pin "2") (pinfunction "2_2") (pintype "passive"))
      (node (ref "T4") (pin "3") (pinfunction "D_3") (pintype "passive"))
      (node (ref "TVS4") (pin "A") (pinfunction "A_A") (pintype "passive"))
    )
    (net (code "58") (name "Net-(T4-G)") (class "Default")
      (node (ref "RB4") (pin "2") (pinfunction "2_2") (pintype "passive"))
      (node (ref "RT4") (pin "1") (pinfunction "1_1") (pintype "passive"))
      (node (ref "T4") (pin "1") (pinfunction "G_1") (pintype "passive"))
    )
    (net (code "59") (name "Net-(T5-D)") (class "Default")
      (node (ref "S02") (pin "5") (pinfunction "5_5") (pintype "passive"))
      (node (ref "SP5") (pin "2") (pinfunction "2_2") (pintype "passive"))
      (node (ref "T5") (pin "3") (pinfunction "D_3") (pintype "passive"))
      (node (ref "TVS5") (pin "A") (pinfunction "A_A") (pintype "passive"))
    )
    (net (code "60") (name "Net-(T5-G)") (class "Default")
      (node (ref "RB5") (pin "2") (pinfunction "2_2") (pintype "passive"))
      (node (ref "RT5") (pin "1") (pinfunction "1_1") (pintype "passive"))
      (node (ref "T5") (pin "1") (pinfunction "G_1") (pintype "passive"))
    )
    (net (code "61") (name "Net-(T6-D)") (class "Default")
      (node (ref "S02") (pin "6") (pinfunction "6_6") (pintype "passive"))
      (node (ref "SP6") (pin "2") (pinfunction "2_2") (pintype "passive"))
      (node (ref "T6") (pin "3") (pinfunction "D_3") (pintype "passive"))
      (node (ref "TVS6") (pin "A") (pinfunction "A_A") (pintype "passive"))
    )
    (net (code "62") (name "Net-(T6-G)") (class "Default")
      (node (ref "RB6") (pin "2") (pinfunction "2_2") (pintype "passive"))
      (node (ref "RT6") (pin "1") (pinfunction "1_1") (pintype "passive"))
      (node (ref "T6") (pin "1") (pinfunction "G_1") (pintype "passive"))
    )
    (net (code "63") (name "Net-(T7-D)") (class "Default")
      (node (ref "S02") (pin "7") (pinfunction "7_7") (pintype "passive"))
      (node (ref "SP7") (pin "2") (pinfunction "2_2") (pintype "passive"))
      (node (ref "T7") (pin "3") (pinfunction "D_3") (pintype "passive"))
      (node (ref "TVS7") (pin "A") (pinfunction "A_A") (pintype "passive"))
    )
    (net (code "64") (name "Net-(T7-G)") (class "Default")
      (node (ref "RB7") (pin "2") (pinfunction "2_2") (pintype "passive"))
      (node (ref "RT7") (pin "1") (pinfunction "1_1") (pintype "passive"))
      (node (ref "T7") (pin "1") (pinfunction "G_1") (pintype "passive"))
    )
    (net (code "65") (name "Net-(T8-D)") (class "Default")
      (node (ref "S02") (pin "8") (pinfunction "8_8") (pintype "passive"))
      (node (ref "SP8") (pin "2") (pinfunction "2_2") (pintype "passive"))
      (node (ref "T8") (pin "3") (pinfunction "D_3") (pintype "passive"))
      (node (ref "TVS8") (pin "A") (pinfunction "A_A") (pintype "passive"))
    )
    (net (code "66") (name "Net-(T8-G)") (class "Default")
      (node (ref "RB8") (pin "2") (pinfunction "2_2") (pintype "passive"))
      (node (ref "RT8") (pin "1") (pinfunction "1_1") (pintype "passive"))
      (node (ref "T8") (pin "1") (pinfunction "G_1") (pintype "passive"))
    )
    (net (code "67") (name "unconnected-(J1-PadGNDBREAK)") (class "Default")
      (node (ref "J1") (pin "GNDBREAK") (pinfunction "GNDBREAK_GNDBREAK") (pintype "bidirectional"))
    )
    (net (code "68") (name "unconnected-(JCON-Pad11)") (class "Default")
      (node (ref "JCON") (pin "11") (pinfunction "11_11") (pintype "passive"))
    )
    (net (code "69") (name "unconnected-(JCON-Pad12)") (class "Default")
      (node (ref "JCON") (pin "12") (pinfunction "12_12") (pintype "passive"))
    )
    (net (code "70") (name "unconnected-(JEXT-Pad1)") (class "Default")
      (node (ref "JEXT") (pin "1") (pinfunction "1_1") (pintype "passive"))
    )
    (net (code "71") (name "unconnected-(JEXT-Pad2)") (class "Default")
      (node (ref "JEXT") (pin "2") (pinfunction "2_2") (pintype "passive"))
    )
    (net (code "72") (name "unconnected-(JEXT-Pad5)") (class "Default")
      (node (ref "JEXT") (pin "5") (pinfunction "5_5") (pintype "passive"))
    )
    (net (code "73") (name "unconnected-(JEXT-Pad6)") (class "Default")
      (node (ref "JEXT") (pin "6") (pinfunction "6_6") (pintype "passive"))
    )
    (net (code "74") (name "unconnected-(PCF8574-NC1-Pad3)") (class "Default")
      (node (ref "PCF8574") (pin "3") (pinfunction "NC1_3") (pintype "bidirectional"))
    )
    (net (code "75") (name "unconnected-(PCF8574-NC3-Pad13)") (class "Default")
      (node (ref "PCF8574") (pin "13") (pinfunction "NC3_13") (pintype "bidirectional"))
    )
    (net (code "76") (name "unconnected-(PCF8574-NC4-Pad18)") (class "Default")
      (node (ref "PCF8574") (pin "18") (pinfunction "NC4_18") (pintype "bidirectional"))
    )
    (net (code "77") (name "unconnected-(PCF8574-~{INT}-Pad1)") (class "Default")
      (node (ref "PCF8574") (pin "1") (pinfunction "~{INT}_1") (pintype "bidirectional"))
    )
  )
)
